# ECE180DA.net
KiCad netlist of a schematic drawn in EAGLE
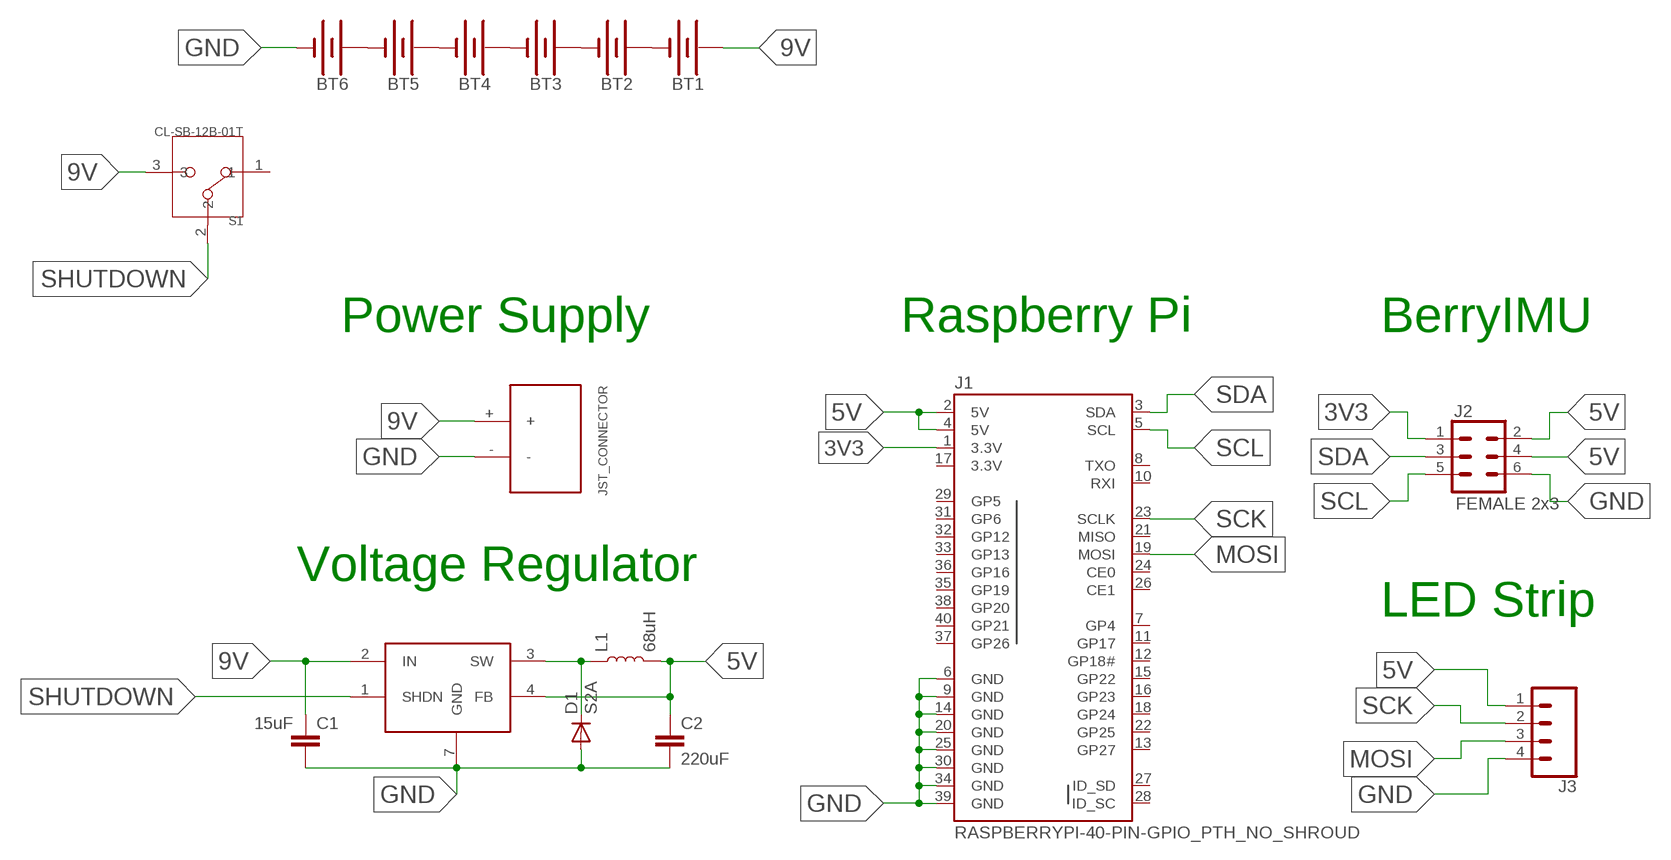
[diagram p0: schematic, sheet 1]

(export (version "E")
  (design (tool "Eeschema 10.0.6"))
  (components
    (comp (ref "BT1")
      (value "BATTERY-AA")
      (footprint "eagle-import:BATTERY-AA")
      (libsource (lib "eagle-import") (part "BATTERY-AA"))
    )
    (comp (ref "BT2")
      (value "BATTERY-AA")
      (footprint "eagle-import:BATTERY-AA")
      (libsource (lib "eagle-import") (part "BATTERY-AA"))
    )
    (comp (ref "BT3")
      (value "BATTERY-AA")
      (footprint "eagle-import:BATTERY-AA")
      (libsource (lib "eagle-import") (part "BATTERY-AA"))
    )
    (comp (ref "BT4")
      (value "BATTERY-AA")
      (footprint "eagle-import:BATTERY-AA")
      (libsource (lib "eagle-import") (part "BATTERY-AA"))
    )
    (comp (ref "BT5")
      (value "BATTERY-AA")
      (footprint "eagle-import:BATTERY-AA")
      (libsource (lib "eagle-import") (part "BATTERY-AA"))
    )
    (comp (ref "BT6")
      (value "BATTERY-AA")
      (footprint "eagle-import:BATTERY-AA")
      (libsource (lib "eagle-import") (part "BATTERY-AA"))
    )
    (comp (ref "C1")
      (value "15uF")
      (footprint "eagle-import:C0603K")
      (libsource (lib "eagle-import") (part "C-EUC0603K"))
    )
    (comp (ref "C2")
      (value "220uF")
      (footprint "eagle-import:C1206K")
      (libsource (lib "eagle-import") (part "C-EUC1206K"))
    )
    (comp (ref "D1")
      (value "S2A")
      (footprint "eagle-import:DO214AA")
      (fields (field (name "MF") "Fairchild"))
      (libsource (lib "eagle-import") (part "S2A"))
    )
    (comp (ref "J1")
      (value "RASPBERRYPI-40-PIN-GPIO_PTH_NO_SHROUD")
      (footprint "eagle-import:2X20")
      (libsource (lib "eagle-import") (part "RASPBERRYPI-40-PIN-GPIO_PTH_NO_SHROUD"))
    )
    (comp (ref "J2")
      (value "FEMALE 2x3")
      (footprint "eagle-import:2X3")
      (libsource (lib "eagle-import") (part "CONN_03X2FEMALE"))
    )
    (comp (ref "J3")
      (value "CONN_04")
      (footprint "eagle-import:1X04")
      (libsource (lib "eagle-import") (part "CONN_04"))
    )
    (comp (ref "L1")
      (value "68uH")
      (footprint "eagle-import:0603")
      (libsource (lib "eagle-import") (part "INDUCTOR-0603-33NH"))
    )
    (comp (ref "S1")
      (value "CL-SB-12B-01T")
      (footprint "eagle-import:CL-SB-12B")
      (fields (field (name "MF") "Nidec Copal"))
      (libsource (lib "eagle-import") (part "CL-SB-12B-01T"))
    )
    (comp (ref "U$1")
      (value "MIC4680")
      (footprint "eagle-import:SOIC-8")
      (fields (field (name "MF") "Micrel"))
      (libsource (lib "eagle-import") (part "MIC4680"))
    )
    (comp (ref "U$3")
      (value "JST_CONNECTOR_FEMALE")
      (footprint "eagle-import:JST_CONNECTOR_FEMALE")
      (libsource (lib "eagle-import") (part "JST_CONNECTOR_FEMALE"))
    )
  )
  (nets
    (net (code "1") (name "/3.3V") (class "Default")
      (node (ref "J1") (pin "17") (pinfunction "3.3V_17") (pintype "power_in"))
    )
    (net (code "2") (name "3V3") (class "Default")
      (node (ref "J1") (pin "1") (pinfunction "3.3V_1") (pintype "power_in"))
      (node (ref "J2") (pin "1") (pinfunction "1_1") (pintype "bidirectional"))
    )
    (net (code "3") (name "5V") (class "Default")
      (node (ref "C2") (pin "1") (pinfunction "1_1") (pintype "passive"))
      (node (ref "J1") (pin "2") (pinfunction "5V_2") (pintype "power_in"))
      (node (ref "J1") (pin "4") (pinfunction "5V_4") (pintype "power_in"))
      (node (ref "J2") (pin "2") (pinfunction "2_2") (pintype "bidirectional"))
      (node (ref "J2") (pin "4") (pinfunction "4_4") (pintype "bidirectional"))
      (node (ref "J3") (pin "1") (pinfunction "1_1") (pintype "passive"))
      (node (ref "L1") (pin "2") (pinfunction "2_2") (pintype "passive"))
      (node (ref "U$1") (pin "4") (pinfunction "FB_4") (pintype "bidirectional"))
    )
    (net (code "4") (name "9V") (class "Default")
      (node (ref "BT1") (pin "PWR@1") (pinfunction "+_PWR@1") (pintype "power_in"))
      (node (ref "C1") (pin "1") (pinfunction "1_1") (pintype "passive"))
      (node (ref "S1") (pin "3") (pinfunction "3_3") (pintype "bidirectional"))
      (node (ref "U$1") (pin "2") (pinfunction "IN_2") (pintype "bidirectional"))
      (node (ref "U$3") (pin "+") (pinfunction "+_+") (pintype "bidirectional"))
    )
    (net (code "5") (name "GND") (class "Default")
      (node (ref "BT6") (pin "GND@1") (pinfunction "-_GND@1") (pintype "power_in"))
      (node (ref "C1") (pin "2") (pinfunction "2_2") (pintype "passive"))
      (node (ref "C2") (pin "2") (pinfunction "2_2") (pintype "passive"))
      (node (ref "D1") (pin "A") (pinfunction "A_A") (pintype "passive"))
      (node (ref "J1") (pin "14") (pinfunction "GND_14") (pintype "power_in"))
      (node (ref "J1") (pin "20") (pinfunction "GND_20") (pintype "power_in"))
      (node (ref "J1") (pin "25") (pinfunction "GND_25") (pintype "power_in"))
      (node (ref "J1") (pin "30") (pinfunction "GND_30") (pintype "power_in"))
      (node (ref "J1") (pin "34") (pinfunction "GND_34") (pintype "power_in"))
      (node (ref "J1") (pin "39") (pinfunction "GND_39") (pintype "power_in"))
      (node (ref "J1") (pin "6") (pinfunction "GND_6") (pintype "power_in"))
      (node (ref "J1") (pin "9") (pinfunction "GND_9") (pintype "power_in"))
      (node (ref "J2") (pin "6") (pinfunction "6_6") (pintype "bidirectional"))
      (node (ref "J3") (pin "4") (pinfunction "4_4") (pintype "passive"))
      (node (ref "U$1") (pin "5") (pinfunction "GND_5") (pintype "power_in"))
      (node (ref "U$1") (pin "6") (pinfunction "GND_6") (pintype "power_in"))
      (node (ref "U$1") (pin "7") (pinfunction "GND_7") (pintype "power_in"))
      (node (ref "U$1") (pin "8") (pinfunction "GND_8") (pintype "power_in"))
      (node (ref "U$3") (pin "-") (pinfunction "-_-") (pintype "bidirectional"))
    )
    (net (code "6") (name "MOSI") (class "Default")
      (node (ref "J1") (pin "19") (pinfunction "MOSI_19") (pintype "output"))
      (node (ref "J3") (pin "3") (pinfunction "3_3") (pintype "passive"))
    )
    (net (code "7") (name "Net-(BT1--)") (class "Default")
      (node (ref "BT1") (pin "GND@1") (pinfunction "-_GND@1") (pintype "power_in"))
      (node (ref "BT2") (pin "PWR@1") (pinfunction "+_PWR@1") (pintype "power_in"))
    )
    (net (code "8") (name "Net-(BT2--)") (class "Default")
      (node (ref "BT2") (pin "GND@1") (pinfunction "-_GND@1") (pintype "power_in"))
      (node (ref "BT3") (pin "PWR@1") (pinfunction "+_PWR@1") (pintype "power_in"))
    )
    (net (code "9") (name "Net-(BT3--)") (class "Default")
      (node (ref "BT3") (pin "GND@1") (pinfunction "-_GND@1") (pintype "power_in"))
      (node (ref "BT4") (pin "PWR@1") (pinfunction "+_PWR@1") (pintype "power_in"))
    )
    (net (code "10") (name "Net-(BT4--)") (class "Default")
      (node (ref "BT4") (pin "GND@1") (pinfunction "-_GND@1") (pintype "power_in"))
      (node (ref "BT5") (pin "PWR@1") (pinfunction "+_PWR@1") (pintype "power_in"))
    )
    (net (code "11") (name "Net-(BT5--)") (class "Default")
      (node (ref "BT5") (pin "GND@1") (pinfunction "-_GND@1") (pintype "power_in"))
      (node (ref "BT6") (pin "PWR@1") (pinfunction "+_PWR@1") (pintype "power_in"))
    )
    (net (code "12") (name "Net-(U$1-SW)") (class "Default")
      (node (ref "D1") (pin "C") (pinfunction "C_C") (pintype "passive"))
      (node (ref "L1") (pin "1") (pinfunction "1_1") (pintype "passive"))
      (node (ref "U$1") (pin "3") (pinfunction "SW_3") (pintype "bidirectional"))
    )
    (net (code "13") (name "SCK") (class "Default")
      (node (ref "J1") (pin "23") (pinfunction "SCLK_23") (pintype "output"))
      (node (ref "J3") (pin "2") (pinfunction "2_2") (pintype "passive"))
    )
    (net (code "14") (name "SCL") (class "Default")
      (node (ref "J1") (pin "5") (pinfunction "SCL_5") (pintype "bidirectional"))
      (node (ref "J2") (pin "5") (pinfunction "5_5") (pintype "bidirectional"))
    )
    (net (code "15") (name "SDA") (class "Default")
      (node (ref "J1") (pin "3") (pinfunction "SDA_3") (pintype "bidirectional"))
      (node (ref "J2") (pin "3") (pinfunction "3_3") (pintype "bidirectional"))
    )
    (net (code "16") (name "SHUTDOWN") (class "Default")
      (node (ref "S1") (pin "2") (pinfunction "2_2") (pintype "bidirectional"))
      (node (ref "U$1") (pin "1") (pinfunction "SHDN_1") (pintype "bidirectional"))
    )
    (net (code "17") (name "unconnected-(J1-CE0-Pad24)") (class "Default")
      (node (ref "J1") (pin "24") (pinfunction "CE0_24") (pintype "output"))
    )
    (net (code "18") (name "unconnected-(J1-CE1-Pad26)") (class "Default")
      (node (ref "J1") (pin "26") (pinfunction "CE1_26") (pintype "output"))
    )
    (net (code "19") (name "unconnected-(J1-GP4-Pad7)") (class "Default")
      (node (ref "J1") (pin "7") (pinfunction "GP4_7") (pintype "bidirectional"))
    )
    (net (code "20") (name "unconnected-(J1-GP5-Pad29)") (class "Default")
      (node (ref "J1") (pin "29") (pinfunction "GP5_29") (pintype "bidirectional"))
    )
    (net (code "21") (name "unconnected-(J1-GP6-Pad31)") (class "Default")
      (node (ref "J1") (pin "31") (pinfunction "GP6_31") (pintype "bidirectional"))
    )
    (net (code "22") (name "unconnected-(J1-GP12-Pad32)") (class "Default")
      (node (ref "J1") (pin "32") (pinfunction "GP12_32") (pintype "bidirectional"))
    )
    (net (code "23") (name "unconnected-(J1-GP13-Pad33)") (class "Default")
      (node (ref "J1") (pin "33") (pinfunction "GP13_33") (pintype "bidirectional"))
    )
    (net (code "24") (name "unconnected-(J1-GP16-Pad36)") (class "Default")
      (node (ref "J1") (pin "36") (pinfunction "GP16_36") (pintype "bidirectional"))
    )
    (net (code "25") (name "unconnected-(J1-GP17-Pad11)") (class "Default")
      (node (ref "J1") (pin "11") (pinfunction "GP17_11") (pintype "bidirectional"))
    )
    (net (code "26") (name "unconnected-(J1-GP18#-Pad12)") (class "Default")
      (node (ref "J1") (pin "12") (pinfunction "GP18#_12") (pintype "bidirectional"))
    )
    (net (code "27") (name "unconnected-(J1-GP19-Pad35)") (class "Default")
      (node (ref "J1") (pin "35") (pinfunction "GP19_35") (pintype "bidirectional"))
    )
    (net (code "28") (name "unconnected-(J1-GP20-Pad38)") (class "Default")
      (node (ref "J1") (pin "38") (pinfunction "GP20_38") (pintype "bidirectional"))
    )
    (net (code "29") (name "unconnected-(J1-GP21-Pad40)") (class "Default")
      (node (ref "J1") (pin "40") (pinfunction "GP21_40") (pintype "bidirectional"))
    )
    (net (code "30") (name "unconnected-(J1-GP22-Pad15)") (class "Default")
      (node (ref "J1") (pin "15") (pinfunction "GP22_15") (pintype "bidirectional"))
    )
    (net (code "31") (name "unconnected-(J1-GP23-Pad16)") (class "Default")
      (node (ref "J1") (pin "16") (pinfunction "GP23_16") (pintype "bidirectional"))
    )
    (net (code "32") (name "unconnected-(J1-GP24-Pad18)") (class "Default")
      (node (ref "J1") (pin "18") (pinfunction "GP24_18") (pintype "bidirectional"))
    )
    (net (code "33") (name "unconnected-(J1-GP25-Pad22)") (class "Default")
      (node (ref "J1") (pin "22") (pinfunction "GP25_22") (pintype "bidirectional"))
    )
    (net (code "34") (name "unconnected-(J1-GP26-Pad37)") (class "Default")
      (node (ref "J1") (pin "37") (pinfunction "GP26_37") (pintype "bidirectional"))
    )
    (net (code "35") (name "unconnected-(J1-GP27-Pad13)") (class "Default")
      (node (ref "J1") (pin "13") (pinfunction "GP27_13") (pintype "bidirectional"))
    )
    (net (code "36") (name "unconnected-(J1-ID_SC-Pad28)") (class "Default")
      (node (ref "J1") (pin "28") (pinfunction "ID_SC_28") (pintype "bidirectional"))
    )
    (net (code "37") (name "unconnected-(J1-ID_SD-Pad27)") (class "Default")
      (node (ref "J1") (pin "27") (pinfunction "ID_SD_27") (pintype "bidirectional"))
    )
    (net (code "38") (name "unconnected-(J1-MISO-Pad21)") (class "Default")
      (node (ref "J1") (pin "21") (pinfunction "MISO_21") (pintype "input"))
    )
    (net (code "39") (name "unconnected-(J1-RXI-Pad10)") (class "Default")
      (node (ref "J1") (pin "10") (pinfunction "RXI_10") (pintype "input"))
    )
    (net (code "40") (name "unconnected-(J1-TXO-Pad8)") (class "Default")
      (node (ref "J1") (pin "8") (pinfunction "TXO_8") (pintype "output"))
    )
    (net (code "41") (name "unconnected-(S1-Pad1)") (class "Default")
      (node (ref "S1") (pin "1") (pinfunction "1_1") (pintype "bidirectional"))
    )
  )
)
